# Sheet1.net
KiCad netlist of a schematic drawn in Altium Designer
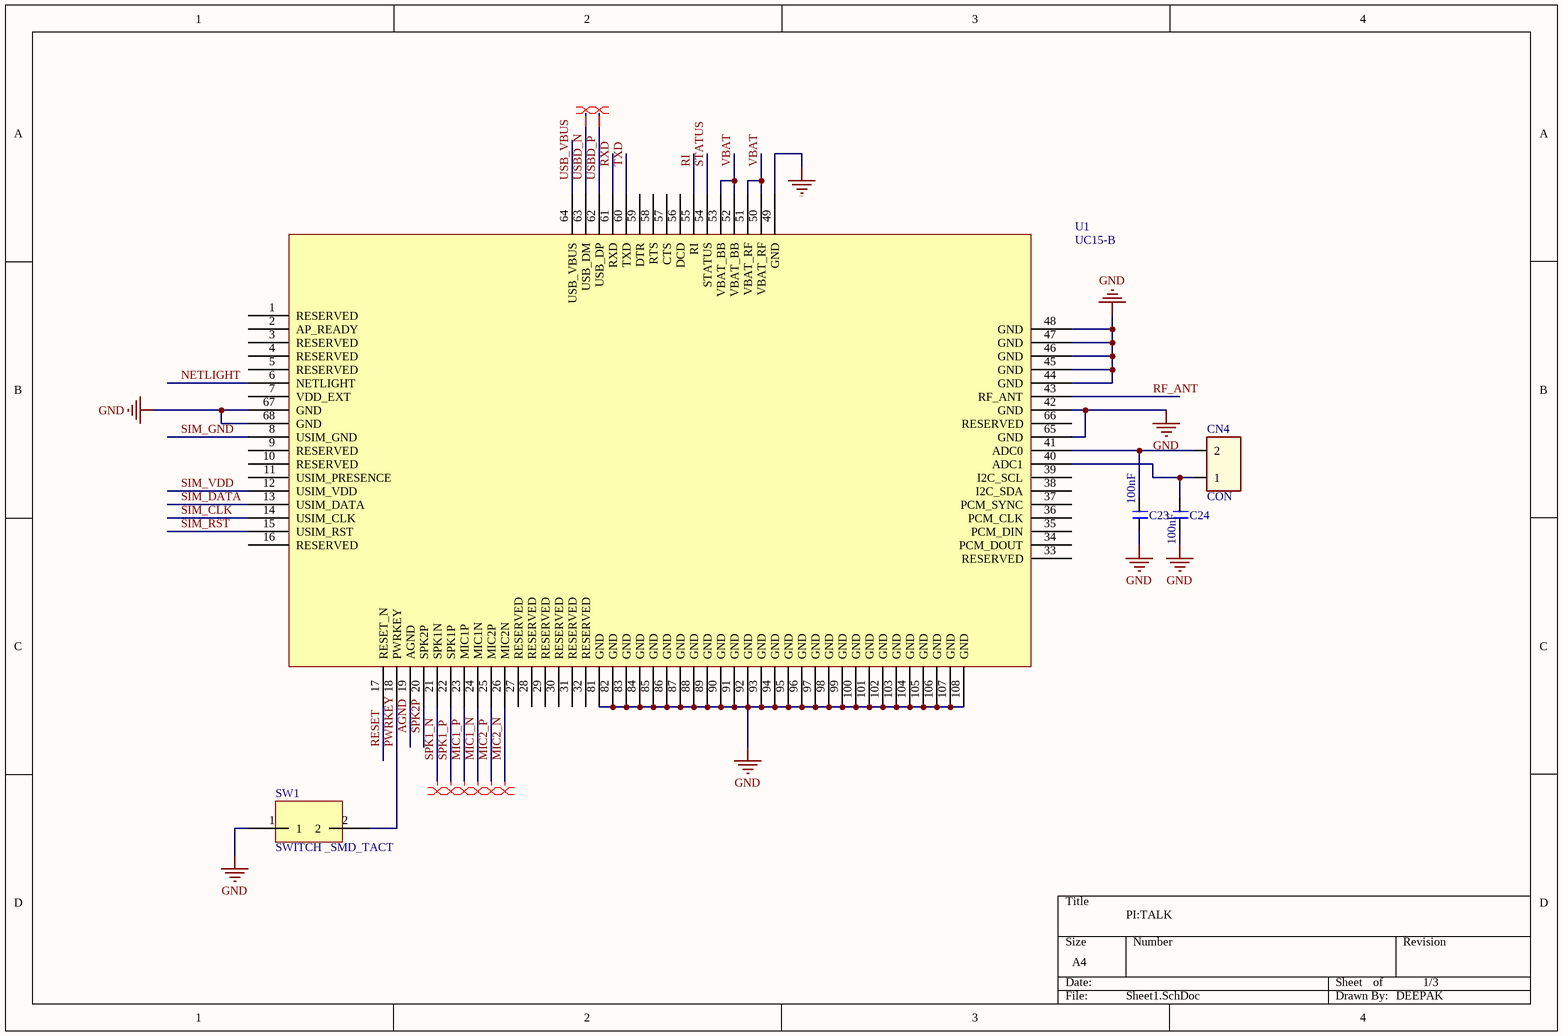
[diagram p0: Sheet1.SchDoc]

(export (version "E")
  (design (tool "Eeschema 10.0.6"))
  (components
    (comp (ref "C23")
      (value "100nF")
      (footprint "CAP_0603_NONPOLAR")
      (libsource (lib "dxp_pasl_lib") (part "CAP_NONPOLAR"))
    )
    (comp (ref "C24")
      (value "100nF")
      (footprint "CAP_0603_NONPOLAR")
      (libsource (lib "dxp_pasl_lib") (part "CAP_NONPOLAR"))
    )
    (comp (ref "CN4") (value "CON") (footprint "CON2_BJ") (libsource (lib "dxp_pasl_lib") (part "CON2")))
    (comp (ref "SW1")
      (value "SWITCH _SMD_TACT")
      (footprint "SWITCH_SMD")
      (libsource (lib "dxp_pasl_lib") (part "SWITCH _SMD_TACT"))
    )
    (comp (ref "U1") (value "UC15-B") (footprint "UC15_B") (libsource (lib "dxp_pasl_lib") (part "UC15")))
  )
  (nets
    (net (code "1") (name "/AGND") (class "Default")
      (node (ref "U1") (pin "19") (pinfunction "AGND_19") (pintype "passive"))
    )
    (net (code "2") (name "/MIC1_N") (class "Default")
      (node (ref "U1") (pin "24") (pinfunction "MIC1N_24") (pintype "passive"))
    )
    (net (code "3") (name "/MIC1_P") (class "Default")
      (node (ref "U1") (pin "23") (pinfunction "MIC1P_23") (pintype "passive"))
    )
    (net (code "4") (name "/MIC2_N") (class "Default")
      (node (ref "U1") (pin "26") (pinfunction "MIC2N_26") (pintype "passive"))
    )
    (net (code "5") (name "/MIC2_P") (class "Default")
      (node (ref "U1") (pin "25") (pinfunction "MIC2P_25") (pintype "passive"))
    )
    (net (code "6") (name "/NETLIGHT") (class "Default")
      (node (ref "U1") (pin "6") (pinfunction "NETLIGHT_6") (pintype "passive"))
    )
    (net (code "7") (name "/PWRKEY") (class "Default")
      (node (ref "SW1") (pin "2") (pinfunction "2_2") (pintype "passive"))
      (node (ref "U1") (pin "18") (pinfunction "PWRKEY_18") (pintype "passive"))
    )
    (net (code "8") (name "/RESET") (class "Default")
      (node (ref "U1") (pin "17") (pinfunction "RESET_N_17") (pintype "passive"))
    )
    (net (code "9") (name "/RF_ANT") (class "Default")
      (node (ref "U1") (pin "43") (pinfunction "RF_ANT_43") (pintype "passive"))
    )
    (net (code "10") (name "/RI") (class "Default")
      (node (ref "U1") (pin "55") (pinfunction "RI_55") (pintype "passive"))
    )
    (net (code "11") (name "/RXD") (class "Default")
      (node (ref "U1") (pin "61") (pinfunction "RXD_61") (pintype "passive"))
    )
    (net (code "12") (name "/SIM_CLK") (class "Default")
      (node (ref "U1") (pin "14") (pinfunction "USIM_CLK_14") (pintype "passive"))
    )
    (net (code "13") (name "/SIM_DATA") (class "Default")
      (node (ref "U1") (pin "13") (pinfunction "USIM_DATA_13") (pintype "passive"))
    )
    (net (code "14") (name "/SIM_GND") (class "Default")
      (node (ref "U1") (pin "8") (pinfunction "USIM_GND_8") (pintype "passive"))
    )
    (net (code "15") (name "/SIM_RST") (class "Default")
      (node (ref "U1") (pin "15") (pinfunction "USIM_RST_15") (pintype "passive"))
    )
    (net (code "16") (name "/SIM_VDD") (class "Default")
      (node (ref "U1") (pin "12") (pinfunction "USIM_VDD_12") (pintype "passive"))
    )
    (net (code "17") (name "/SPK1_N") (class "Default")
      (node (ref "U1") (pin "21") (pinfunction "SPK1N_21") (pintype "passive"))
    )
    (net (code "18") (name "/SPK1_P") (class "Default")
      (node (ref "U1") (pin "22") (pinfunction "SPK1P_22") (pintype "passive"))
    )
    (net (code "19") (name "/SPK2P") (class "Default")
      (node (ref "U1") (pin "20") (pinfunction "SPK2P_20") (pintype "passive"))
    )
    (net (code "20") (name "/STATUS") (class "Default")
      (node (ref "U1") (pin "54") (pinfunction "STATUS_54") (pintype "passive"))
    )
    (net (code "21") (name "/TXD") (class "Default")
      (node (ref "U1") (pin "60") (pinfunction "TXD_60") (pintype "passive"))
    )
    (net (code "22") (name "/USBD_N") (class "Default")
      (node (ref "U1") (pin "63") (pinfunction "USB_DM_63") (pintype "passive"))
    )
    (net (code "23") (name "/USBD_P") (class "Default")
      (node (ref "U1") (pin "62") (pinfunction "USB_DP_62") (pintype "passive"))
    )
    (net (code "24") (name "/USB_VBUS") (class "Default")
      (node (ref "U1") (pin "64") (pinfunction "USB_VBUS_64") (pintype "passive"))
    )
    (net (code "25") (name "/VBAT") (class "Default")
      (node (ref "U1") (pin "50") (pinfunction "VBAT_RF_50") (pintype "passive"))
      (node (ref "U1") (pin "51") (pinfunction "VBAT_RF_51") (pintype "passive"))
      (node (ref "U1") (pin "52") (pinfunction "VBAT_BB_52") (pintype "passive"))
      (node (ref "U1") (pin "53") (pinfunction "VBAT_BB_53") (pintype "passive"))
    )
    (net (code "26") (name "GND") (class "Default")
      (node (ref "C23") (pin "1") (pinfunction "1_1") (pintype "passive"))
      (node (ref "C24") (pin "1") (pinfunction "1_1") (pintype "passive"))
      (node (ref "SW1") (pin "1") (pinfunction "1_1") (pintype "passive"))
      (node (ref "U1") (pin "100") (pinfunction "GND_100") (pintype "passive"))
      (node (ref "U1") (pin "101") (pinfunction "GND_101") (pintype "passive"))
      (node (ref "U1") (pin "102") (pinfunction "GND_102") (pintype "passive"))
      (node (ref "U1") (pin "103") (pinfunction "GND_103") (pintype "passive"))
      (node (ref "U1") (pin "104") (pinfunction "GND_104") (pintype "passive"))
      (node (ref "U1") (pin "105") (pinfunction "GND_105") (pintype "passive"))
      (node (ref "U1") (pin "106") (pinfunction "GND_106") (pintype "passive"))
      (node (ref "U1") (pin "107") (pinfunction "GND_107") (pintype "passive"))
      (node (ref "U1") (pin "108") (pinfunction "GND_108") (pintype "passive"))
      (node (ref "U1") (pin "42") (pinfunction "GND_42") (pintype "passive"))
      (node (ref "U1") (pin "44") (pinfunction "GND_44") (pintype "passive"))
      (node (ref "U1") (pin "45") (pinfunction "GND_45") (pintype "passive"))
      (node (ref "U1") (pin "46") (pinfunction "GND_46") (pintype "passive"))
      (node (ref "U1") (pin "47") (pinfunction "GND_47") (pintype "passive"))
      (node (ref "U1") (pin "48") (pinfunction "GND_48") (pintype "passive"))
      (node (ref "U1") (pin "49") (pinfunction "GND_49") (pintype "passive"))
      (node (ref "U1") (pin "65") (pinfunction "GND_65") (pintype "passive"))
      (node (ref "U1") (pin "67") (pinfunction "GND_67") (pintype "passive"))
      (node (ref "U1") (pin "68") (pinfunction "GND_68") (pintype "passive"))
      (node (ref "U1") (pin "81") (pinfunction "GND_81") (pintype "passive"))
      (node (ref "U1") (pin "82") (pinfunction "GND_82") (pintype "passive"))
      (node (ref "U1") (pin "83") (pinfunction "GND_83") (pintype "passive"))
      (node (ref "U1") (pin "84") (pinfunction "GND_84") (pintype "passive"))
      (node (ref "U1") (pin "85") (pinfunction "GND_85") (pintype "passive"))
      (node (ref "U1") (pin "86") (pinfunction "GND_86") (pintype "passive"))
      (node (ref "U1") (pin "87") (pinfunction "GND_87") (pintype "passive"))
      (node (ref "U1") (pin "88") (pinfunction "GND_88") (pintype "passive"))
      (node (ref "U1") (pin "89") (pinfunction "GND_89") (pintype "passive"))
      (node (ref "U1") (pin "90") (pinfunction "GND_90") (pintype "passive"))
      (node (ref "U1") (pin "91") (pinfunction "GND_91") (pintype "passive"))
      (node (ref "U1") (pin "92") (pinfunction "GND_92") (pintype "passive"))
      (node (ref "U1") (pin "93") (pinfunction "GND_93") (pintype "passive"))
      (node (ref "U1") (pin "94") (pinfunction "GND_94") (pintype "passive"))
      (node (ref "U1") (pin "95") (pinfunction "GND_95") (pintype "passive"))
      (node (ref "U1") (pin "96") (pinfunction "GND_96") (pintype "passive"))
      (node (ref "U1") (pin "97") (pinfunction "GND_97") (pintype "passive"))
      (node (ref "U1") (pin "98") (pinfunction "GND_98") (pintype "passive"))
      (node (ref "U1") (pin "99") (pinfunction "GND_99") (pintype "passive"))
    )
    (net (code "27") (name "Net-(U1-ADC0)") (class "Default")
      (node (ref "C23") (pin "2") (pinfunction "2_2") (pintype "passive"))
      (node (ref "CN4") (pin "2") (pinfunction "2_2") (pintype "passive"))
      (node (ref "U1") (pin "41") (pinfunction "ADC0_41") (pintype "passive"))
    )
    (net (code "28") (name "Net-(U1-ADC1)") (class "Default")
      (node (ref "C24") (pin "2") (pinfunction "2_2") (pintype "passive"))
      (node (ref "CN4") (pin "1") (pinfunction "1_1") (pintype "passive"))
      (node (ref "U1") (pin "40") (pinfunction "ADC1_40") (pintype "passive"))
    )
    (net (code "29") (name "unconnected-(U1-AP_READY-Pad2)") (class "Default")
      (node (ref "U1") (pin "2") (pinfunction "AP_READY_2") (pintype "passive"))
    )
    (net (code "30") (name "unconnected-(U1-CTS-Pad57)") (class "Default")
      (node (ref "U1") (pin "57") (pinfunction "CTS_57") (pintype "passive"))
    )
    (net (code "31") (name "unconnected-(U1-DCD-Pad56)") (class "Default")
      (node (ref "U1") (pin "56") (pinfunction "DCD_56") (pintype "passive"))
    )
    (net (code "32") (name "unconnected-(U1-DTR-Pad59)") (class "Default")
      (node (ref "U1") (pin "59") (pinfunction "DTR_59") (pintype "passive"))
    )
    (net (code "33") (name "unconnected-(U1-I2C_SCL-Pad39)") (class "Default")
      (node (ref "U1") (pin "39") (pinfunction "I2C_SCL_39") (pintype "passive"))
    )
    (net (code "34") (name "unconnected-(U1-I2C_SDA-Pad38)") (class "Default")
      (node (ref "U1") (pin "38") (pinfunction "I2C_SDA_38") (pintype "passive"))
    )
    (net (code "35") (name "unconnected-(U1-PCM_CLK-Pad36)") (class "Default")
      (node (ref "U1") (pin "36") (pinfunction "PCM_CLK_36") (pintype "passive"))
    )
    (net (code "36") (name "unconnected-(U1-PCM_DIN-Pad35)") (class "Default")
      (node (ref "U1") (pin "35") (pinfunction "PCM_DIN_35") (pintype "passive"))
    )
    (net (code "37") (name "unconnected-(U1-PCM_DOUT-Pad34)") (class "Default")
      (node (ref "U1") (pin "34") (pinfunction "PCM_DOUT_34") (pintype "passive"))
    )
    (net (code "38") (name "unconnected-(U1-PCM_SYNC-Pad37)") (class "Default")
      (node (ref "U1") (pin "37") (pinfunction "PCM_SYNC_37") (pintype "passive"))
    )
    (net (code "39") (name "unconnected-(U1-RESERVED-Pad1)") (class "Default")
      (node (ref "U1") (pin "1") (pinfunction "RESERVED_1") (pintype "passive"))
    )
    (net (code "40") (name "unconnected-(U1-RESERVED-Pad3)") (class "Default")
      (node (ref "U1") (pin "3") (pinfunction "RESERVED_3") (pintype "passive"))
    )
    (net (code "41") (name "unconnected-(U1-RESERVED-Pad4)") (class "Default")
      (node (ref "U1") (pin "4") (pinfunction "RESERVED_4") (pintype "passive"))
    )
    (net (code "42") (name "unconnected-(U1-RESERVED-Pad5)") (class "Default")
      (node (ref "U1") (pin "5") (pinfunction "RESERVED_5") (pintype "passive"))
    )
    (net (code "43") (name "unconnected-(U1-RESERVED-Pad9)") (class "Default")
      (node (ref "U1") (pin "9") (pinfunction "RESERVED_9") (pintype "passive"))
    )
    (net (code "44") (name "unconnected-(U1-RESERVED-Pad10)") (class "Default")
      (node (ref "U1") (pin "10") (pinfunction "RESERVED_10") (pintype "passive"))
    )
    (net (code "45") (name "unconnected-(U1-RESERVED-Pad16)") (class "Default")
      (node (ref "U1") (pin "16") (pinfunction "RESERVED_16") (pintype "passive"))
    )
    (net (code "46") (name "unconnected-(U1-RESERVED-Pad27)") (class "Default")
      (node (ref "U1") (pin "27") (pinfunction "RESERVED_27") (pintype "passive"))
    )
    (net (code "47") (name "unconnected-(U1-RESERVED-Pad28)") (class "Default")
      (node (ref "U1") (pin "28") (pinfunction "RESERVED_28") (pintype "passive"))
    )
    (net (code "48") (name "unconnected-(U1-RESERVED-Pad29)") (class "Default")
      (node (ref "U1") (pin "29") (pinfunction "RESERVED_29") (pintype "passive"))
    )
    (net (code "49") (name "unconnected-(U1-RESERVED-Pad30)") (class "Default")
      (node (ref "U1") (pin "30") (pinfunction "RESERVED_30") (pintype "passive"))
    )
    (net (code "50") (name "unconnected-(U1-RESERVED-Pad31)") (class "Default")
      (node (ref "U1") (pin "31") (pinfunction "RESERVED_31") (pintype "passive"))
    )
    (net (code "51") (name "unconnected-(U1-RESERVED-Pad32)") (class "Default")
      (node (ref "U1") (pin "32") (pinfunction "RESERVED_32") (pintype "passive"))
    )
    (net (code "52") (name "unconnected-(U1-RESERVED-Pad33)") (class "Default")
      (node (ref "U1") (pin "33") (pinfunction "RESERVED_33") (pintype "passive"))
    )
    (net (code "53") (name "unconnected-(U1-RESERVED-Pad66)") (class "Default")
      (node (ref "U1") (pin "66") (pinfunction "RESERVED_66") (pintype "passive"))
    )
    (net (code "54") (name "unconnected-(U1-RTS-Pad58)") (class "Default")
      (node (ref "U1") (pin "58") (pinfunction "RTS_58") (pintype "passive"))
    )
    (net (code "55") (name "unconnected-(U1-USIM_PRESENCE-Pad11)") (class "Default")
      (node (ref "U1") (pin "11") (pinfunction "USIM_PRESENCE_11") (pintype "passive"))
    )
    (net (code "56") (name "unconnected-(U1-VDD_EXT-Pad7)") (class "Default")
      (node (ref "U1") (pin "7") (pinfunction "VDD_EXT_7") (pintype "passive"))
    )
  )
)
